# Level_Shifter.net
KiCad netlist of a schematic drawn in Altium Designer
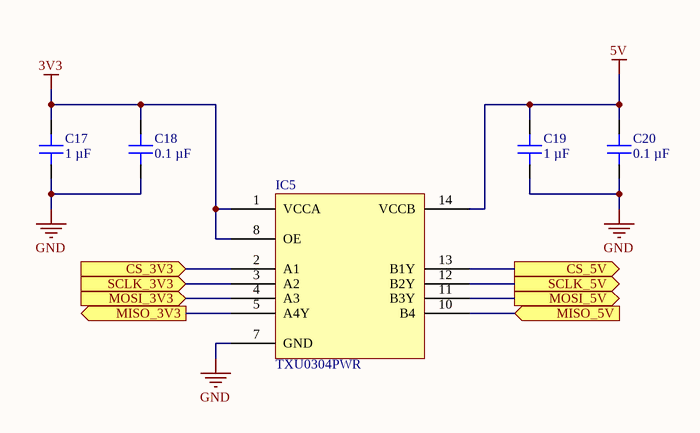
[diagram p0: Level Shifter.SchDoc]

(export (version "E")
  (design (tool "Eeschema 10.0.6"))
  (components
    (comp (ref "C17")
      (value "1 µF")
      (footprint "CAP 0603_1608")
      (description "CAP CER 1UF 25V X7R 0603")
      (fields
        (field (name "PART NUMBER") "GCM188R71E105KA64D")
        (field (name "MANUFACTURER") "Murata Electronics")
      )
      (libsource (lib "altiumlibrary.com") (part "Capacitor"))
    )
    (comp (ref "C18")
      (value "0.1 µF")
      (footprint "CAP 0603_1608")
      (description "CAP CER 0.1UF 50V X7R 0603")
      (fields
        (field (name "PART NUMBER") "CL10B104KB8NNNC")
        (field (name "MANUFACTURER") "Samsung Electro-Mechanics")
      )
      (libsource (lib "altiumlibrary.com") (part "Capacitor"))
    )
    (comp (ref "C19")
      (value "1 µF")
      (footprint "CAP 0603_1608")
      (description "CAP CER 1UF 25V X7R 0603")
      (fields
        (field (name "PART NUMBER") "GCM188R71E105KA64D")
        (field (name "MANUFACTURER") "Murata Electronics")
      )
      (libsource (lib "altiumlibrary.com") (part "Capacitor"))
    )
    (comp (ref "C20")
      (value "0.1 µF")
      (footprint "CAP 0603_1608")
      (description "CAP CER 0.1UF 50V X7R 0603")
      (fields
        (field (name "PART NUMBER") "CL10B104KB8NNNC")
        (field (name "MANUFACTURER") "Samsung Electro-Mechanics")
      )
      (libsource (lib "altiumlibrary.com") (part "Capacitor"))
    )
    (comp (ref "IC5")
      (value "TXU0304PWR")
      (footprint "TI TSSOP-14 PW")
      (description "IC TRANSLATOR UNIDIR 14TSSOP")
      (fields (field (name "MANUFACTURER") "Texas Instruments"))
      (libsource (lib "altiumlibrary.com") (part "TI TXU0304 14-TSSOP"))
    )
  )
  (nets
    (net (code "1") (name "/CS_3V3") (class "Default")
      (node (ref "IC5") (pin "2") (pinfunction "A1_2") (pintype "passive"))
    )
    (net (code "2") (name "/CS_5V") (class "Default")
      (node (ref "IC5") (pin "13") (pinfunction "B1Y_13") (pintype "passive"))
    )
    (net (code "3") (name "/MISO_3V3") (class "Default")
      (node (ref "IC5") (pin "5") (pinfunction "A4Y_5") (pintype "passive"))
    )
    (net (code "4") (name "/MISO_5V") (class "Default")
      (node (ref "IC5") (pin "10") (pinfunction "B4_10") (pintype "passive"))
    )
    (net (code "5") (name "/MOSI_3V3") (class "Default")
      (node (ref "IC5") (pin "4") (pinfunction "A3_4") (pintype "passive"))
    )
    (net (code "6") (name "/MOSI_5V") (class "Default")
      (node (ref "IC5") (pin "11") (pinfunction "B3Y_11") (pintype "passive"))
    )
    (net (code "7") (name "/SCLK_3V3") (class "Default")
      (node (ref "IC5") (pin "3") (pinfunction "A2_3") (pintype "passive"))
    )
    (net (code "8") (name "/SCLK_5V") (class "Default")
      (node (ref "IC5") (pin "12") (pinfunction "B2Y_12") (pintype "passive"))
    )
    (net (code "9") (name "3V3") (class "Default")
      (node (ref "C17") (pin "2") (pinfunction "2_2") (pintype "passive"))
      (node (ref "C18") (pin "1") (pinfunction "1_1") (pintype "passive"))
      (node (ref "IC5") (pin "1") (pinfunction "VCCA_1") (pintype "passive"))
      (node (ref "IC5") (pin "8") (pinfunction "OE_8") (pintype "passive"))
    )
    (net (code "10") (name "5V") (class "Default")
      (node (ref "C19") (pin "2") (pinfunction "2_2") (pintype "passive"))
      (node (ref "C20") (pin "1") (pinfunction "1_1") (pintype "passive"))
      (node (ref "IC5") (pin "14") (pinfunction "VCCB_14") (pintype "passive"))
    )
    (net (code "11") (name "GND") (class "Default")
      (node (ref "C17") (pin "1") (pinfunction "1_1") (pintype "passive"))
      (node (ref "C18") (pin "2") (pinfunction "2_2") (pintype "passive"))
      (node (ref "C19") (pin "1") (pinfunction "1_1") (pintype "passive"))
      (node (ref "C20") (pin "2") (pinfunction "2_2") (pintype "passive"))
      (node (ref "IC5") (pin "7") (pinfunction "GND_7") (pintype "passive"))
    )
  )
)
